# arduino-minimul-atmega328p.net
KiCad netlist of a schematic drawn in EAGLE
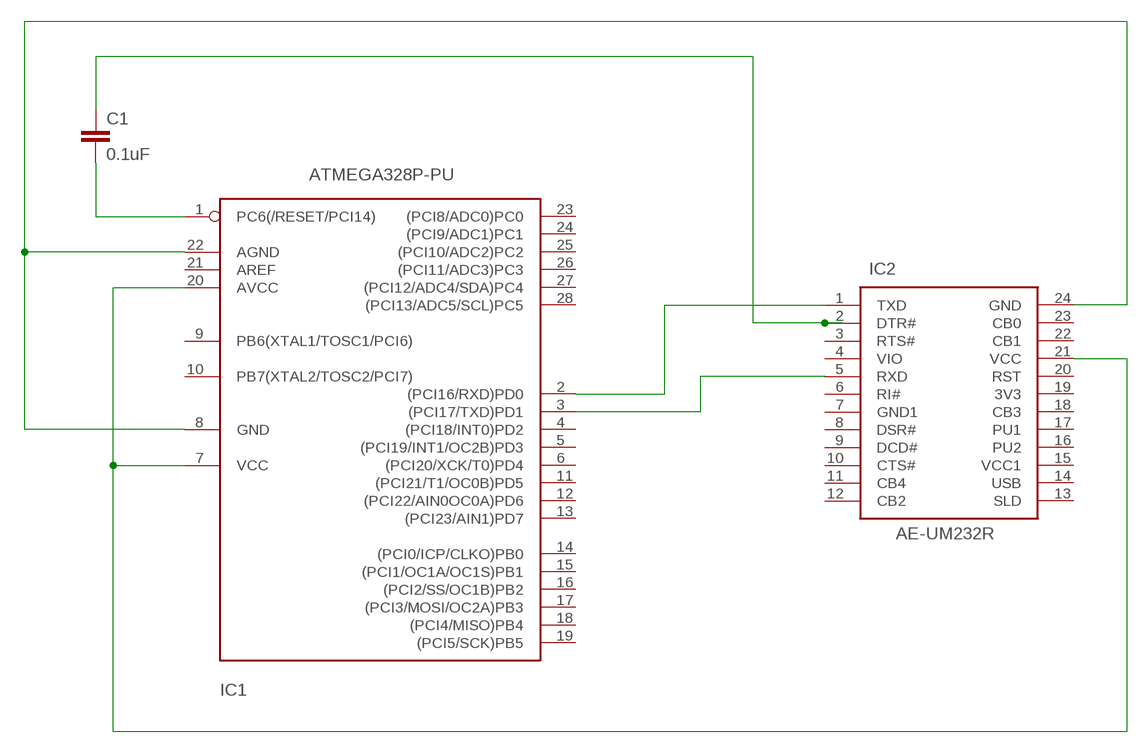
[diagram p0: schematic, sheet 1]

(export (version "E")
  (design (tool "Eeschema 10.0.6"))
  (components
    (comp (ref "C1")
      (value "0.1uF")
      (footprint "eagle-import:C025-024X044")
      (libsource (lib "eagle-import") (part "C-EU025-024X044"))
    )
    (comp (ref "IC1")
      (value "ATMEGA328P-PU")
      (footprint "eagle-import:DIL28-3")
      (libsource (lib "eagle-import") (part "ATMEGA328P-PU"))
    )
    (comp (ref "IC2")
      (value "AE-UM232R")
      (footprint "eagle-import:AE-UM232R")
      (libsource (lib "eagle-import") (part "AE-UM232R"))
    )
  )
  (nets
    (net (code "1") (name "/GND1") (class "Default")
      (node (ref "IC2") (pin "7") (pinfunction "GND1_7") (pintype "power_in"))
    )
    (net (code "2") (name "/VCC1") (class "Default")
      (node (ref "IC2") (pin "15") (pinfunction "VCC1_15") (pintype "power_in"))
    )
    (net (code "3") (name "Net-(IC1-(PCI16{slash}RXD)PD0)") (class "Default")
      (node (ref "IC1") (pin "2") (pinfunction "(PCI16/RXD)PD0_2") (pintype "bidirectional"))
      (node (ref "IC2") (pin "1") (pinfunction "TXD_1") (pintype "bidirectional"))
    )
    (net (code "4") (name "Net-(IC1-(PCI17{slash}TXD)PD1)") (class "Default")
      (node (ref "IC1") (pin "3") (pinfunction "(PCI17/TXD)PD1_3") (pintype "bidirectional"))
      (node (ref "IC2") (pin "5") (pinfunction "RXD_5") (pintype "bidirectional"))
    )
    (net (code "5") (name "Net-(IC1-AGND)") (class "Default")
      (node (ref "IC1") (pin "22") (pinfunction "AGND_22") (pintype "bidirectional"))
      (node (ref "IC1") (pin "8") (pinfunction "GND_8") (pintype "bidirectional"))
      (node (ref "IC2") (pin "24") (pinfunction "GND_24") (pintype "power_in"))
    )
    (net (code "6") (name "Net-(IC1-AVCC)") (class "Default")
      (node (ref "IC1") (pin "20") (pinfunction "AVCC_20") (pintype "bidirectional"))
      (node (ref "IC1") (pin "7") (pinfunction "VCC_7") (pintype "bidirectional"))
      (node (ref "IC2") (pin "21") (pinfunction "VCC_21") (pintype "power_in"))
    )
    (net (code "7") (name "Net-(IC1-PC6({slash}RESET{slash}PCI14))") (class "Default")
      (node (ref "C1") (pin "2") (pinfunction "2_2") (pintype "passive"))
      (node (ref "IC1") (pin "1") (pinfunction "PC6(/RESET/PCI14)_1") (pintype "bidirectional"))
    )
    (net (code "8") (name "Net-(IC2-DTR#)") (class "Default")
      (node (ref "C1") (pin "1") (pinfunction "1_1") (pintype "passive"))
      (node (ref "IC2") (pin "2") (pinfunction "DTR#_2") (pintype "bidirectional"))
    )
    (net (code "9") (name "unconnected-(IC1-(PCI0{slash}ICP{slash}CLKO)PB0-Pad14)") (class "Default")
      (node (ref "IC1") (pin "14") (pinfunction "(PCI0/ICP/CLKO)PB0_14") (pintype "bidirectional"))
    )
    (net (code "10") (name "unconnected-(IC1-(PCI1{slash}OC1A{slash}OC1S)PB1-Pad15)") (class "Default")
      (node (ref "IC1") (pin "15") (pinfunction "(PCI1/OC1A/OC1S)PB1_15") (pintype "bidirectional"))
    )
    (net (code "11") (name "unconnected-(IC1-(PCI2{slash}SS{slash}OC1B)PB2-Pad16)") (class "Default")
      (node (ref "IC1") (pin "16") (pinfunction "(PCI2/SS/OC1B)PB2_16") (pintype "bidirectional"))
    )
    (net (code "12") (name "unconnected-(IC1-(PCI3{slash}MOSI{slash}OC2A)PB3-Pad17)") (class "Default")
      (node (ref "IC1") (pin "17") (pinfunction "(PCI3/MOSI/OC2A)PB3_17") (pintype "bidirectional"))
    )
    (net (code "13") (name "unconnected-(IC1-(PCI4{slash}MISO)PB4-Pad18)") (class "Default")
      (node (ref "IC1") (pin "18") (pinfunction "(PCI4/MISO)PB4_18") (pintype "bidirectional"))
    )
    (net (code "14") (name "unconnected-(IC1-(PCI5{slash}SCK)PB5-Pad19)") (class "Default")
      (node (ref "IC1") (pin "19") (pinfunction "(PCI5/SCK)PB5_19") (pintype "bidirectional"))
    )
    (net (code "15") (name "unconnected-(IC1-(PCI8{slash}ADC0)PC0-Pad23)") (class "Default")
      (node (ref "IC1") (pin "23") (pinfunction "(PCI8/ADC0)PC0_23") (pintype "bidirectional"))
    )
    (net (code "16") (name "unconnected-(IC1-(PCI9{slash}ADC1)PC1-Pad24)") (class "Default")
      (node (ref "IC1") (pin "24") (pinfunction "(PCI9/ADC1)PC1_24") (pintype "bidirectional"))
    )
    (net (code "17") (name "unconnected-(IC1-(PCI10{slash}ADC2)PC2-Pad25)") (class "Default")
      (node (ref "IC1") (pin "25") (pinfunction "(PCI10/ADC2)PC2_25") (pintype "bidirectional"))
    )
    (net (code "18") (name "unconnected-(IC1-(PCI11{slash}ADC3)PC3-Pad26)") (class "Default")
      (node (ref "IC1") (pin "26") (pinfunction "(PCI11/ADC3)PC3_26") (pintype "bidirectional"))
    )
    (net (code "19") (name "unconnected-(IC1-(PCI12{slash}ADC4{slash}SDA)PC4-Pad27)") (class "Default")
      (node (ref "IC1") (pin "27") (pinfunction "(PCI12/ADC4/SDA)PC4_27") (pintype "bidirectional"))
    )
    (net (code "20") (name "unconnected-(IC1-(PCI13{slash}ADC5{slash}SCL)PC5-Pad28)") (class "Default")
      (node (ref "IC1") (pin "28") (pinfunction "(PCI13/ADC5/SCL)PC5_28") (pintype "bidirectional"))
    )
    (net (code "21") (name "unconnected-(IC1-(PCI18{slash}INT0)PD2-Pad4)") (class "Default")
      (node (ref "IC1") (pin "4") (pinfunction "(PCI18/INT0)PD2_4") (pintype "bidirectional"))
    )
    (net (code "22") (name "unconnected-(IC1-(PCI19{slash}INT1{slash}OC2B)PD3-Pad5)") (class "Default")
      (node (ref "IC1") (pin "5") (pinfunction "(PCI19/INT1/OC2B)PD3_5") (pintype "bidirectional"))
    )
    (net (code "23") (name "unconnected-(IC1-(PCI20{slash}XCK{slash}T0)PD4-Pad6)") (class "Default")
      (node (ref "IC1") (pin "6") (pinfunction "(PCI20/XCK/T0)PD4_6") (pintype "bidirectional"))
    )
    (net (code "24") (name "unconnected-(IC1-(PCI21{slash}T1{slash}OC0B)PD5-Pad11)") (class "Default")
      (node (ref "IC1") (pin "11") (pinfunction "(PCI21/T1/OC0B)PD5_11") (pintype "bidirectional"))
    )
    (net (code "25") (name "unconnected-(IC1-(PCI22{slash}AIN0OC0A)PD6-Pad12)") (class "Default")
      (node (ref "IC1") (pin "12") (pinfunction "(PCI22/AIN0OC0A)PD6_12") (pintype "bidirectional"))
    )
    (net (code "26") (name "unconnected-(IC1-(PCI23{slash}AIN1)PD7-Pad13)") (class "Default")
      (node (ref "IC1") (pin "13") (pinfunction "(PCI23/AIN1)PD7_13") (pintype "bidirectional"))
    )
    (net (code "27") (name "unconnected-(IC1-AREF-Pad21)") (class "Default")
      (node (ref "IC1") (pin "21") (pinfunction "AREF_21") (pintype "bidirectional"))
    )
    (net (code "28") (name "unconnected-(IC1-PB6(XTAL1{slash}TOSC1{slash}PCI6)-Pad9)") (class "Default")
      (node (ref "IC1") (pin "9") (pinfunction "PB6(XTAL1/TOSC1/PCI6)_9") (pintype "bidirectional"))
    )
    (net (code "29") (name "unconnected-(IC1-PB7(XTAL2{slash}TOSC2{slash}PCI7)-Pad10)") (class "Default")
      (node (ref "IC1") (pin "10") (pinfunction "PB7(XTAL2/TOSC2/PCI7)_10") (pintype "bidirectional"))
    )
    (net (code "30") (name "unconnected-(IC2-3V3-Pad19)") (class "Default")
      (node (ref "IC2") (pin "19") (pinfunction "3V3_19") (pintype "bidirectional"))
    )
    (net (code "31") (name "unconnected-(IC2-CB0-Pad23)") (class "Default")
      (node (ref "IC2") (pin "23") (pinfunction "CB0_23") (pintype "bidirectional"))
    )
    (net (code "32") (name "unconnected-(IC2-CB1-Pad22)") (class "Default")
      (node (ref "IC2") (pin "22") (pinfunction "CB1_22") (pintype "bidirectional"))
    )
    (net (code "33") (name "unconnected-(IC2-CB2-Pad12)") (class "Default")
      (node (ref "IC2") (pin "12") (pinfunction "CB2_12") (pintype "bidirectional"))
    )
    (net (code "34") (name "unconnected-(IC2-CB3-Pad18)") (class "Default")
      (node (ref "IC2") (pin "18") (pinfunction "CB3_18") (pintype "bidirectional"))
    )
    (net (code "35") (name "unconnected-(IC2-CB4-Pad11)") (class "Default")
      (node (ref "IC2") (pin "11") (pinfunction "CB4_11") (pintype "bidirectional"))
    )
    (net (code "36") (name "unconnected-(IC2-CTS#-Pad10)") (class "Default")
      (node (ref "IC2") (pin "10") (pinfunction "CTS#_10") (pintype "bidirectional"))
    )
    (net (code "37") (name "unconnected-(IC2-DCD#-Pad9)") (class "Default")
      (node (ref "IC2") (pin "9") (pinfunction "DCD#_9") (pintype "bidirectional"))
    )
    (net (code "38") (name "unconnected-(IC2-DSR#-Pad8)") (class "Default")
      (node (ref "IC2") (pin "8") (pinfunction "DSR#_8") (pintype "bidirectional"))
    )
    (net (code "39") (name "unconnected-(IC2-PU1-Pad17)") (class "Default")
      (node (ref "IC2") (pin "17") (pinfunction "PU1_17") (pintype "bidirectional"))
    )
    (net (code "40") (name "unconnected-(IC2-PU2-Pad16)") (class "Default")
      (node (ref "IC2") (pin "16") (pinfunction "PU2_16") (pintype "bidirectional"))
    )
    (net (code "41") (name "unconnected-(IC2-RI#-Pad6)") (class "Default")
      (node (ref "IC2") (pin "6") (pinfunction "RI#_6") (pintype "bidirectional"))
    )
    (net (code "42") (name "unconnected-(IC2-RST-Pad20)") (class "Default")
      (node (ref "IC2") (pin "20") (pinfunction "RST_20") (pintype "bidirectional"))
    )
    (net (code "43") (name "unconnected-(IC2-RTS#-Pad3)") (class "Default")
      (node (ref "IC2") (pin "3") (pinfunction "RTS#_3") (pintype "bidirectional"))
    )
    (net (code "44") (name "unconnected-(IC2-SLD-Pad13)") (class "Default")
      (node (ref "IC2") (pin "13") (pinfunction "SLD_13") (pintype "bidirectional"))
    )
    (net (code "45") (name "unconnected-(IC2-USB-Pad14)") (class "Default")
      (node (ref "IC2") (pin "14") (pinfunction "USB_14") (pintype "bidirectional"))
    )
    (net (code "46") (name "unconnected-(IC2-VIO-Pad4)") (class "Default")
      (node (ref "IC2") (pin "4") (pinfunction "VIO_4") (pintype "bidirectional"))
    )
  )
)
